# ups.net
KiCad netlist of a schematic drawn in Altium Designer
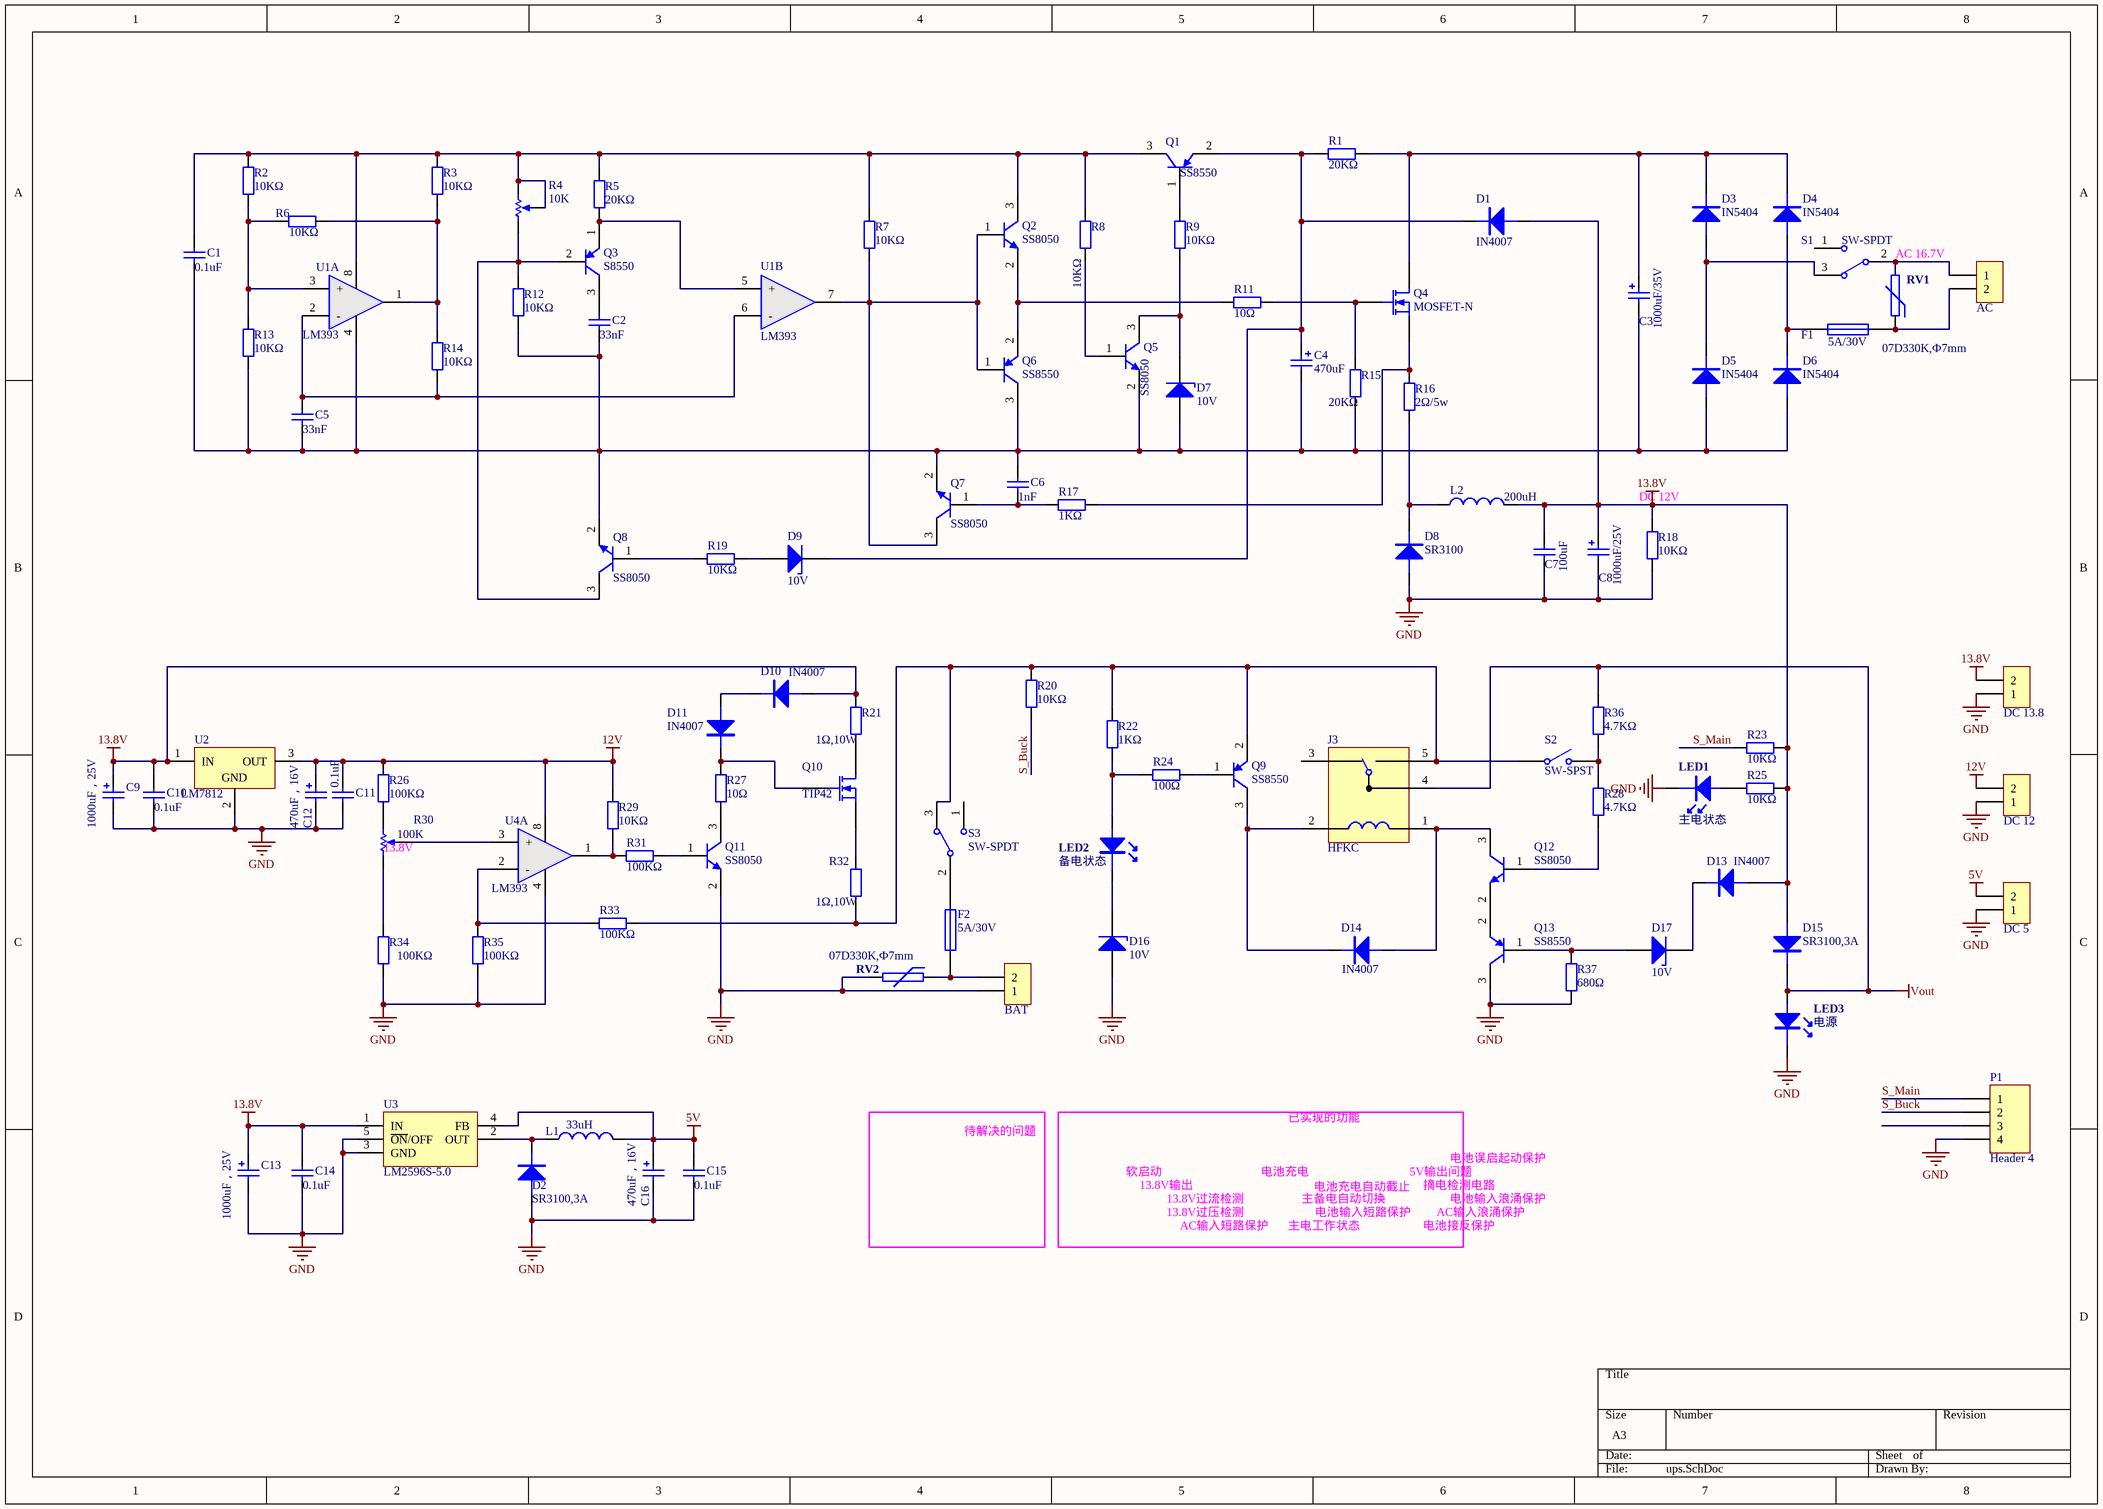
[diagram p0: ups.SchDoc]

(export (version "E")
  (design (tool "Eeschema 10.0.6"))
  (components
    (comp (ref "AC")
      (value "CON2")
      (footprint "CON-2-5.08")
      (description "2EDGR/2EDGK-5.08-2P,DEGSON")
      (libsource (lib "") (part "CON2_1"))
    )
    (comp (ref "BAT")
      (value "CON2")
      (footprint "CON-2-5.08")
      (description "2EDGR/2EDGK-5.08-2P,DEGSON")
      (libsource (lib "IoT-A28LI V1.00") (part "CON2"))
    )
    (comp (ref "C1")
      (value "0.1uF")
      (footprint "C-RAD")
      (description "电容")
      (fields (field (name "PUBLISHER") "Altium Limited"))
      (libsource (lib "liuxiaolong") (part "Cap"))
    )
    (comp (ref "C2")
      (value "33nF")
      (footprint "C-RAD")
      (description "电容")
      (fields (field (name "PUBLISHER") "Altium Limited"))
      (libsource (lib "liuxiaolong") (part "Cap"))
    )
    (comp (ref "C3")
      (value "1000uF/35V")
      (footprint "C-RB-18")
      (description "大容量电容")
      (fields (field (name "PUBLISHER") "Altium Limited"))
      (libsource (lib "liuxiaolong") (part "Cap Pol3"))
    )
    (comp (ref "C4")
      (value "470uF")
      (footprint "C-RB-10")
      (description "大容量电容")
      (fields (field (name "PUBLISHER") "Altium Limited"))
      (libsource (lib "liuxiaolong") (part "Cap Pol3"))
    )
    (comp (ref "C5")
      (value "33nF")
      (footprint "C-RAD")
      (description "电容")
      (fields (field (name "PUBLISHER") "Altium Limited"))
      (libsource (lib "liuxiaolong") (part "Cap"))
    )
    (comp (ref "C6")
      (value "1nF")
      (footprint "C-RAD")
      (description "电容")
      (fields (field (name "PUBLISHER") "Altium Limited"))
      (libsource (lib "liuxiaolong") (part "Cap"))
    )
    (comp (ref "C7")
      (value "100uF")
      (footprint "C-RB-8")
      (description "电容")
      (fields (field (name "PUBLISHER") "Altium Limited"))
      (libsource (lib "liuxiaolong") (part "Cap"))
    )
    (comp (ref "C8")
      (value "1000uF/25V")
      (footprint "C-RB-12")
      (description "大容量电容")
      (fields (field (name "PUBLISHER") "Altium Limited"))
      (libsource (lib "liuxiaolong") (part "Cap Pol3"))
    )
    (comp (ref "C9")
      (value "1000uF，25V")
      (footprint "C-RB-10")
      (description "大容量电容")
      (fields (field (name "PUBLISHER") "Altium Limited"))
      (libsource (lib "liuxiaolong") (part "Cap Pol3"))
    )
    (comp (ref "C10")
      (value "0.1uF")
      (footprint "C-RAD")
      (description "电容")
      (fields (field (name "PUBLISHER") "Altium Limited"))
      (libsource (lib "liuxiaolong") (part "Cap"))
    )
    (comp (ref "C11")
      (value "0.1uF")
      (footprint "C-RAD")
      (description "电容")
      (fields (field (name "PUBLISHER") "Altium Limited"))
      (libsource (lib "liuxiaolong") (part "Cap"))
    )
    (comp (ref "C12")
      (value "470uF，16V")
      (footprint "C-RB-8")
      (description "大容量电容")
      (fields (field (name "PUBLISHER") "Altium Limited"))
      (libsource (lib "liuxiaolong") (part "Cap Pol3"))
    )
    (comp (ref "C13")
      (value "1000uF，25V")
      (footprint "C-RB-10")
      (description "大容量电容")
      (fields (field (name "PUBLISHER") "Altium Limited"))
      (libsource (lib "liuxiaolong") (part "Cap Pol3"))
    )
    (comp (ref "C14")
      (value "0.1uF")
      (footprint "C-RAD")
      (description "电容")
      (fields (field (name "PUBLISHER") "Altium Limited"))
      (libsource (lib "liuxiaolong") (part "Cap"))
    )
    (comp (ref "C15")
      (value "0.1uF")
      (footprint "C-RAD")
      (description "电容")
      (fields (field (name "PUBLISHER") "Altium Limited"))
      (libsource (lib "liuxiaolong") (part "Cap"))
    )
    (comp (ref "C16")
      (value "470uF，16V")
      (footprint "C-RB-8")
      (description "大容量电容")
      (fields (field (name "PUBLISHER") "Altium Limited"))
      (libsource (lib "liuxiaolong") (part "Cap Pol3"))
    )
    (comp (ref "D1")
      (value "IN4007")
      (footprint "DO-41")
      (description "二极管")
      (libsource (lib "liuxiaolong") (part "DIODE"))
    )
    (comp (ref "D2") (value "SR3100,3A") (footprint "DO-201AD") (libsource (lib "xiaofang") (part "DIODE")))
    (comp (ref "D3")
      (value "IN5404")
      (footprint "DO-201AD")
      (description "二极管")
      (libsource (lib "liuxiaolong") (part "DIODE"))
    )
    (comp (ref "D4")
      (value "IN5404")
      (footprint "DO-201AD")
      (description "二极管")
      (libsource (lib "liuxiaolong") (part "DIODE"))
    )
    (comp (ref "D5")
      (value "IN5404")
      (footprint "DO-201AD")
      (description "二极管")
      (libsource (lib "liuxiaolong") (part "DIODE"))
    )
    (comp (ref "D6")
      (value "IN5404")
      (footprint "DO-201AD")
      (description "二极管")
      (libsource (lib "liuxiaolong") (part "DIODE"))
    )
    (comp (ref "D7")
      (value "10V")
      (footprint "DIODE-AXL")
      (description "稳压二极管")
      (fields (field (name "Comment") "Diode-Z") (field (name "PUBLISHER") "Altium Limited"))
      (libsource (lib "fszhang") (part "Diode-Z"))
    )
    (comp (ref "D8")
      (value "SR3100")
      (footprint "DO-201AD")
      (description "二极管")
      (libsource (lib "liuxiaolong") (part "DIODE"))
    )
    (comp (ref "D9")
      (value "10V")
      (footprint "DIODE-AXL")
      (description "稳压二极管")
      (fields (field (name "Comment") "Diode-Z") (field (name "PUBLISHER") "Altium Limited"))
      (libsource (lib "fszhang") (part "Diode-Z"))
    )
    (comp (ref "D10")
      (value "IN4007")
      (footprint "DO-41")
      (description "二极管")
      (libsource (lib "liuxiaolong") (part "DIODE"))
    )
    (comp (ref "D11")
      (value "IN4007")
      (footprint "DO-41")
      (description "二极管")
      (libsource (lib "liuxiaolong") (part "DIODE"))
    )
    (comp (ref "D13")
      (value "IN4007")
      (footprint "DO-41")
      (description "二极管")
      (libsource (lib "liuxiaolong") (part "DIODE"))
    )
    (comp (ref "D14")
      (value "IN4007")
      (footprint "DO-41")
      (description "二极管")
      (libsource (lib "liuxiaolong") (part "DIODE"))
    )
    (comp (ref "D15")
      (value "SR3100,3A")
      (footprint "DO-201AD")
      (description "二极管")
      (libsource (lib "liuxiaolong") (part "DIODE"))
    )
    (comp (ref "D16")
      (value "10V")
      (footprint "DIODE-AXL")
      (description "稳压二极管")
      (fields (field (name "Comment") "Diode-Z") (field (name "PUBLISHER") "Altium Limited"))
      (libsource (lib "fszhang") (part "Diode-Z"))
    )
    (comp (ref "D17")
      (value "10V")
      (footprint "DIODE-AXL")
      (description "稳压二极管")
      (fields (field (name "Comment") "Diode-Z") (field (name "PUBLISHER") "Altium Limited"))
      (libsource (lib "fszhang") (part "Diode-Z"))
    )
    (comp (ref "DC 5")
      (value "CON2")
      (footprint "CON-2-5.08")
      (description "2EDGR/2EDGK-5.08-2P,DEGSON")
      (libsource (lib "IoT-A28LI V1.00") (part "CON2"))
    )
    (comp (ref "DC 12")
      (value "CON2")
      (footprint "CON-2-5.08")
      (description "2EDGR/2EDGK-5.08-2P,DEGSON")
      (libsource (lib "IoT-A28LI V1.00") (part "CON2"))
    )
    (comp (ref "DC 13.8")
      (value "CON2")
      (footprint "CON-2-5.08")
      (description "2EDGR/2EDGK-5.08-2P,DEGSON")
      (libsource (lib "IoT-A28LI V1.00") (part "CON2"))
    )
    (comp (ref "F1")
      (value "5A/30V")
      (footprint "BLX-A")
      (description "Fuse")
      (fields (field (name "PUBLISHER") "Altium Limited"))
      (libsource (lib "Miscellaneous Devices") (part "Fuse 1"))
    )
    (comp (ref "F2")
      (value "5A/30V")
      (footprint "PIN-W2/E2.8")
      (description "Fuse")
      (fields (field (name "PUBLISHER") "Altium Limited"))
      (libsource (lib "Miscellaneous Devices") (part "Fuse 1"))
    )
    (comp (ref "J3")
      (value "HFKC")
      (footprint "HF3FF-12")
      (description "单刀双掷继电器")
      (libsource (lib "fszhang") (part "HFKC"))
    )
    (comp (ref "L1") (value "33uH") (footprint "C-RB-8") (libsource (lib "xiaofang") (part "INDUCTOR")))
    (comp (ref "L2") (value "200uH") (footprint "C-RB-8") (libsource (lib "liuxiaolong") (part "INDUCTOR")))
    (comp (ref "LED1")
      (value "主电状态")
      (footprint "LED_A2")
      (description "红色,0603,0603,*,RoHS")
      (fields (field (name "Comment") "Error"))
      (libsource (lib "IoT-A28LI V1.00") (part "LED1"))
    )
    (comp (ref "LED2")
      (value "备电状态")
      (footprint "LED_A2")
      (description "红色,0603,0603,*,RoHS")
      (fields (field (name "Comment") "Error"))
      (libsource (lib "IoT-A28LI V1.00") (part "LED1"))
    )
    (comp (ref "LED3")
      (value "电源")
      (footprint "LED_A2")
      (description "红色,0603,0603,*,RoHS")
      (fields (field (name "Comment") "Error"))
      (libsource (lib "IoT-A28LI V1.00") (part "LED1"))
    )
    (comp (ref "P1")
      (value "Header 4")
      (footprint "HDR1X4")
      (description "Header, 4-Pin")
      (fields (field (name "PUBLISHER") "Altium Limited"))
      (libsource (lib "Miscellaneous Connectors") (part "Header 4"))
    )
    (comp (ref "Q1")
      (value "SS8550")
      (footprint "TO-92-3")
      (description "PNP贴片三极管")
      (fields (field (name "PUBLISHER") "Altium Limited"))
      (libsource (lib "fszhang") (part "SS8550"))
    )
    (comp (ref "Q2")
      (value "SS8050")
      (footprint "TO-92-3")
      (description "NPN贴片三极管")
      (fields (field (name "PUBLISHER") "Altium Limited"))
      (libsource (lib "fszhang") (part "SS8050"))
    )
    (comp (ref "Q3")
      (value "S8550")
      (footprint "TO-92-3")
      (description "PNP三极管")
      (fields (field (name "PUBLISHER") "Altium Limited"))
      (libsource (lib "fszhang") (part "S8550"))
    )
    (comp (ref "Q4")
      (value "MOSFET-N")
      (footprint "TO-220-3")
      (description "N-Channel MOSFET")
      (fields (field (name "PUBLISHER") "Altium Limited"))
      (libsource (lib "Miscellaneous Devices") (part "MOSFET-N"))
    )
    (comp (ref "Q5")
      (value "SS8050")
      (footprint "TO-92-3")
      (description "NPN贴片三极管")
      (fields (field (name "PUBLISHER") "Altium Limited"))
      (libsource (lib "fszhang") (part "SS8050"))
    )
    (comp (ref "Q6")
      (value "SS8550")
      (footprint "TO-92-3")
      (description "PNP贴片三极管")
      (fields (field (name "PUBLISHER") "Altium Limited"))
      (libsource (lib "fszhang") (part "SS8550"))
    )
    (comp (ref "Q7")
      (value "SS8050")
      (footprint "TO-92-3")
      (description "NPN贴片三极管")
      (fields (field (name "PUBLISHER") "Altium Limited"))
      (libsource (lib "fszhang") (part "SS8050"))
    )
    (comp (ref "Q8")
      (value "SS8050")
      (footprint "TO-92-3")
      (description "NPN贴片三极管")
      (fields (field (name "PUBLISHER") "Altium Limited"))
      (libsource (lib "fszhang") (part "SS8050"))
    )
    (comp (ref "Q9")
      (value "SS8550")
      (footprint "TO-92-3")
      (description "PNP贴片三极管")
      (fields (field (name "PUBLISHER") "Altium Limited"))
      (libsource (lib "fszhang") (part "SS8550"))
    )
    (comp (ref "Q10")
      (value "TIP42")
      (footprint "TO-220-3")
      (description "N-Channel MOSFET")
      (fields (field (name "PUBLISHER") "Altium Limited"))
      (libsource (lib "Miscellaneous Devices") (part "MOSFET-N"))
    )
    (comp (ref "Q11")
      (value "SS8050")
      (footprint "TO-92-3")
      (description "NPN贴片三极管")
      (fields (field (name "PUBLISHER") "Altium Limited"))
      (libsource (lib "fszhang") (part "SS8050"))
    )
    (comp (ref "Q12")
      (value "SS8050")
      (footprint "TO-92-3")
      (description "NPN贴片三极管")
      (fields (field (name "PUBLISHER") "Altium Limited"))
      (libsource (lib "fszhang") (part "SS8050"))
    )
    (comp (ref "Q13")
      (value "SS8550")
      (footprint "TO-92-3")
      (description "PNP贴片三极管")
      (fields (field (name "PUBLISHER") "Altium Limited"))
      (libsource (lib "fszhang") (part "SS8550"))
    )
    (comp (ref "R1")
      (value "20KΩ")
      (footprint "AXIAL-0.4")
      (description "电阻")
      (fields (field (name "PUBLISHER") "Altium Limited"))
      (libsource (lib "") (part "Res2_2"))
    )
    (comp (ref "R2")
      (value "10KΩ")
      (footprint "AXIAL-0.4")
      (description "电阻")
      (fields (field (name "PUBLISHER") "Altium Limited"))
      (libsource (lib "") (part "Res2_1"))
    )
    (comp (ref "R3")
      (value "10KΩ")
      (footprint "AXIAL-0.4")
      (description "电阻")
      (fields (field (name "PUBLISHER") "Altium Limited"))
      (libsource (lib "") (part "Res2_1"))
    )
    (comp (ref "R4")
      (value "10K")
      (footprint "VR_A1")
      (description "精密可调电阻")
      (fields (field (name "Comment") "RPot") (field (name "PUBLISHER") "Altium Limited"))
      (libsource (lib "fszhang") (part "RPot"))
    )
    (comp (ref "R5")
      (value "20KΩ")
      (footprint "AXIAL-0.4")
      (description "电阻")
      (fields (field (name "PUBLISHER") "Altium Limited"))
      (libsource (lib "") (part "Res2_1"))
    )
    (comp (ref "R6")
      (value "10KΩ")
      (footprint "AXIAL-0.4")
      (description "电阻")
      (fields (field (name "PUBLISHER") "Altium Limited"))
      (libsource (lib "") (part "Res2_3"))
    )
    (comp (ref "R7")
      (value "10KΩ")
      (footprint "AXIAL-0.4")
      (description "电阻")
      (fields (field (name "PUBLISHER") "Altium Limited"))
      (libsource (lib "") (part "Res2_1"))
    )
    (comp (ref "R8")
      (value "10KΩ")
      (footprint "AXIAL-0.4")
      (description "电阻")
      (fields (field (name "PUBLISHER") "Altium Limited"))
      (libsource (lib "liuxiaolong") (part "Res2"))
    )
    (comp (ref "R9")
      (value "10KΩ")
      (footprint "AXIAL-0.4")
      (description "电阻")
      (fields (field (name "PUBLISHER") "Altium Limited"))
      (libsource (lib "liuxiaolong") (part "Res2"))
    )
    (comp (ref "R11")
      (value "10Ω")
      (footprint "AXIAL-0.4")
      (description "电阻")
      (fields (field (name "PUBLISHER") "Altium Limited"))
      (libsource (lib "") (part "Res2_2"))
    )
    (comp (ref "R12")
      (value "10KΩ")
      (footprint "AXIAL-0.4")
      (description "电阻")
      (fields (field (name "PUBLISHER") "Altium Limited"))
      (libsource (lib "") (part "Res2_1"))
    )
    (comp (ref "R13")
      (value "10KΩ")
      (footprint "AXIAL-0.4")
      (description "电阻")
      (fields (field (name "PUBLISHER") "Altium Limited"))
      (libsource (lib "") (part "Res2_1"))
    )
    (comp (ref "R14")
      (value "10KΩ")
      (footprint "AXIAL-0.4")
      (description "电阻")
      (fields (field (name "PUBLISHER") "Altium Limited"))
      (libsource (lib "") (part "Res2_1"))
    )
    (comp (ref "R15")
      (value "20KΩ")
      (footprint "AXIAL-0.4")
      (description "电阻")
      (fields (field (name "PUBLISHER") "Altium Limited"))
      (libsource (lib "liuxiaolong") (part "Res2"))
    )
    (comp (ref "R16")
      (value "2Ω/5w")
      (footprint "AXIAL-1.0")
      (description "电阻")
      (fields (field (name "PUBLISHER") "Altium Limited"))
      (libsource (lib "liuxiaolong") (part "Res2"))
    )
    (comp (ref "R17")
      (value "1KΩ")
      (footprint "AXIAL-0.4")
      (description "电阻")
      (fields (field (name "PUBLISHER") "Altium Limited"))
      (libsource (lib "") (part "Res2_2"))
    )
    (comp (ref "R18")
      (value "10KΩ")
      (footprint "AXIAL-0.4")
      (description "电阻")
      (fields (field (name "PUBLISHER") "Altium Limited"))
      (libsource (lib "") (part "Res2_3"))
    )
    (comp (ref "R19")
      (value "10KΩ")
      (footprint "AXIAL-0.4")
      (description "电阻")
      (fields (field (name "PUBLISHER") "Altium Limited"))
      (libsource (lib "") (part "Res2_2"))
    )
    (comp (ref "R20")
      (value "10KΩ")
      (footprint "AXIAL-0.4")
      (description "电阻")
      (fields (field (name "PUBLISHER") "Altium Limited"))
      (libsource (lib "") (part "Res2_3"))
    )
    (comp (ref "R21")
      (value "1Ω,10W")
      (footprint "AXIAL-1.0")
      (description "电阻")
      (fields (field (name "PUBLISHER") "Altium Limited"))
      (libsource (lib "liuxiaolong") (part "Res2"))
    )
    (comp (ref "R22")
      (value "1KΩ")
      (footprint "AXIAL-0.4")
      (description "电阻")
      (fields (field (name "PUBLISHER") "Altium Limited"))
      (libsource (lib "") (part "Res2_3"))
    )
    (comp (ref "R23")
      (value "10KΩ")
      (footprint "AXIAL-0.4")
      (description "电阻")
      (fields (field (name "PUBLISHER") "Altium Limited"))
      (libsource (lib "liuxiaolong") (part "Res2"))
    )
    (comp (ref "R24")
      (value "100Ω")
      (footprint "AXIAL-0.4")
      (description "电阻")
      (fields (field (name "PUBLISHER") "Altium Limited"))
      (libsource (lib "") (part "Res2_1"))
    )
    (comp (ref "R25")
      (value "10KΩ")
      (footprint "AXIAL-0.4")
      (description "电阻")
      (fields (field (name "PUBLISHER") "Altium Limited"))
      (libsource (lib "liuxiaolong") (part "Res2"))
    )
    (comp (ref "R26")
      (value "100KΩ")
      (footprint "AXIAL-0.4")
      (description "电阻")
      (fields (field (name "PUBLISHER") "Altium Limited"))
      (libsource (lib "") (part "Res2_1"))
    )
    (comp (ref "R27")
      (value "10Ω")
      (footprint "AXIAL-0.4")
      (description "电阻")
      (fields (field (name "PUBLISHER") "Altium Limited"))
      (libsource (lib "liuxiaolong") (part "Res2"))
    )
    (comp (ref "R28")
      (value "4.7KΩ")
      (footprint "AXIAL-0.4")
      (description "电阻")
      (fields (field (name "PUBLISHER") "Altium Limited"))
      (libsource (lib "") (part "Res2_2"))
    )
    (comp (ref "R29")
      (value "10KΩ")
      (footprint "AXIAL-0.4")
      (description "电阻")
      (fields (field (name "PUBLISHER") "Altium Limited"))
      (libsource (lib "") (part "Res2_1"))
    )
    (comp (ref "R30")
      (value "100K")
      (footprint "VR_A1")
      (description "精密可调电阻")
      (fields (field (name "Comment") "RPot") (field (name "PUBLISHER") "Altium Limited"))
      (libsource (lib "fszhang") (part "RPot"))
    )
    (comp (ref "R31")
      (value "100KΩ")
      (footprint "AXIAL-0.4")
      (description "电阻")
      (fields (field (name "PUBLISHER") "Altium Limited"))
      (libsource (lib "") (part "Res2_2"))
    )
    (comp (ref "R32")
      (value "1Ω,10W")
      (footprint "AXIAL-1.0")
      (description "电阻")
      (fields (field (name "PUBLISHER") "Altium Limited"))
      (libsource (lib "liuxiaolong") (part "Res2"))
    )
    (comp (ref "R33")
      (value "100KΩ")
      (footprint "AXIAL-0.4")
      (description "电阻")
      (fields (field (name "PUBLISHER") "Altium Limited"))
      (libsource (lib "") (part "Res2_2"))
    )
    (comp (ref "R34")
      (value "100KΩ")
      (footprint "AXIAL-0.4")
      (description "电阻")
      (fields (field (name "PUBLISHER") "Altium Limited"))
      (libsource (lib "") (part "Res2_1"))
    )
    (comp (ref "R35")
      (value "100KΩ")
      (footprint "AXIAL-0.4")
      (description "电阻")
      (fields (field (name "PUBLISHER") "Altium Limited"))
      (libsource (lib "") (part "Res2_1"))
    )
    (comp (ref "R36")
      (value "4.7KΩ")
      (footprint "AXIAL-0.4")
      (description "电阻")
      (fields (field (name "PUBLISHER") "Altium Limited"))
      (libsource (lib "") (part "Res2_2"))
    )
    (comp (ref "R37")
      (value "680Ω")
      (footprint "AXIAL-0.4")
      (description "电阻")
      (fields (field (name "PUBLISHER") "Altium Limited"))
      (libsource (lib "") (part "Res2_3"))
    )
    (comp (ref "RV1")
      (value "07D330K,Ф7mm")
      (footprint "AX-5P-9DX4.6T")
      (description "220KD07,Ф8×3mm,RoHS")
      (libsource (lib "IoT-A28LI V1.00") (part "RES4"))
    )
    (comp (ref "RV2")
      (value "07D330K,Ф7mm")
      (footprint "AX-5P-9DX4.6T")
      (description "220KD07,Ф8×3mm,RoHS")
      (libsource (lib "IoT-A28LI V1.00") (part "RES4"))
    )
    (comp (ref "S1")
      (value "SW-SPDT")
      (footprint "SWITCH_A3")
      (description "开关")
      (fields (field (name "PUBLISHER") "Altium Limited"))
      (libsource (lib "fszhang") (part "SW-SPDT"))
    )
    (comp (ref "S2")
      (value "SW-SPST")
      (footprint "SW_4")
      (description "Single-Pole, Single-Throw Switch")
      (fields (field (name "PUBLISHER") "Altium Limited"))
      (libsource (lib "Miscellaneous Devices") (part "SW-SPST"))
    )
    (comp (ref "S3")
      (value "SW-SPDT")
      (footprint "SWITCH_A3")
      (description "开关")
      (fields (field (name "PUBLISHER") "Altium Limited"))
      (libsource (lib "fszhang") (part "SW-SPDT"))
    )
    (comp (ref "U1")
      (value "LM393")
      (footprint "DIP-8")
      (description "比较器，2")
      (libsource (lib "liuxiaolong") (part "LM393"))
    )
    (comp (ref "U2")
      (value "LM7812")
      (footprint "TO-220-3")
      (description "Series 3-Terminal Positive Regulator")
      (fields (field (name "PUBLISHER") "Altium Limited"))
      (libsource (lib "fszhang") (part "LM7818CT"))
    )
    (comp (ref "U3")
      (value "LM2596S-5.0")
      (footprint "TO-220-5A")
      (description "Simple Switcher Power Converter 150 kHz 3A Step Down Voltage Regulator")
      (fields (field (name "PUBLISHER") "Altium Limited"))
      (libsource (lib "电路扫描原理图") (part "LM2596S-5.0"))
    )
    (comp (ref "U4")
      (value "LM393")
      (footprint "DIP-8")
      (description "比较器，2")
      (libsource (lib "liuxiaolong") (part "LM393"))
    )
  )
  (nets
    (net (code "2") (name "/S_Buck") (class "Default")
      (node (ref "P1") (pin "2") (pinfunction "2_2") (pintype "passive"))
      (node (ref "R20") (pin "2") (pinfunction "2_2") (pintype "passive"))
    )
    (net (code "3") (name "/S_Main") (class "Default")
      (node (ref "P1") (pin "1") (pinfunction "1_1") (pintype "passive"))
      (node (ref "R23") (pin "2") (pinfunction "2_2") (pintype "passive"))
    )
    (net (code "4") (name "5V") (class "Default")
      (node (ref "C15") (pin "2") (pinfunction "2_2") (pintype "passive"))
      (node (ref "C16") (pin "1") (pinfunction "1_1") (pintype "passive"))
      (node (ref "DC 5") (pin "2") (pinfunction "2_2") (pintype "passive"))
      (node (ref "L1") (pin "2") (pinfunction "2_2") (pintype "passive"))
      (node (ref "U3") (pin "4") (pinfunction "FB_4") (pintype "passive"))
    )
    (net (code "5") (name "12V") (class "Default")
      (node (ref "C11") (pin "2") (pinfunction "2_2") (pintype "passive"))
      (node (ref "C12") (pin "1") (pinfunction "1_1") (pintype "passive"))
      (node (ref "DC 12") (pin "2") (pinfunction "2_2") (pintype "passive"))
      (node (ref "R26") (pin "2") (pinfunction "2_2") (pintype "passive"))
      (node (ref "R29") (pin "2") (pinfunction "2_2") (pintype "passive"))
      (node (ref "U2") (pin "3") (pinfunction "OUT_3") (pintype "power_in"))
      (node (ref "U4") (pin "8") (pinfunction "VCC_8") (pintype "power_in"))
    )
    (net (code "6") (name "13.8V") (class "Default")
      (node (ref "C10") (pin "2") (pinfunction "2_2") (pintype "passive"))
      (node (ref "C13") (pin "1") (pinfunction "1_1") (pintype "passive"))
      (node (ref "C14") (pin "2") (pinfunction "2_2") (pintype "passive"))
      (node (ref "C7") (pin "2") (pinfunction "2_2") (pintype "passive"))
      (node (ref "C8") (pin "1") (pinfunction "1_1") (pintype "passive"))
      (node (ref "C9") (pin "1") (pinfunction "1_1") (pintype "passive"))
      (node (ref "D1") (pin "1") (pinfunction "A_1") (pintype "passive"))
      (node (ref "D10") (pin "1") (pinfunction "A_1") (pintype "passive"))
      (node (ref "D13") (pin "1") (pinfunction "A_1") (pintype "passive"))
      (node (ref "D15") (pin "1") (pinfunction "A_1") (pintype "passive"))
      (node (ref "DC 13.8") (pin "2") (pinfunction "2_2") (pintype "passive"))
      (node (ref "L2") (pin "1") (pinfunction "1_1") (pintype "passive"))
      (node (ref "R18") (pin "1") (pinfunction "1_1") (pintype "passive"))
      (node (ref "R21") (pin "1") (pinfunction "1_1") (pintype "passive"))
      (node (ref "R23") (pin "1") (pinfunction "1_1") (pintype "passive"))
      (node (ref "R25") (pin "1") (pinfunction "1_1") (pintype "passive"))
      (node (ref "U2") (pin "1") (pinfunction "IN_1") (pintype "power_in"))
      (node (ref "U3") (pin "1") (pinfunction "IN_1") (pintype "power_in"))
    )
    (net (code "7") (name "GND") (class "Default")
      (node (ref "BAT") (pin "1") (pinfunction "1_1") (pintype "passive"))
      (node (ref "C10") (pin "1") (pinfunction "1_1") (pintype "passive"))
      (node (ref "C11") (pin "1") (pinfunction "1_1") (pintype "passive"))
      (node (ref "C12") (pin "2") (pinfunction "2_2") (pintype "passive"))
      (node (ref "C13") (pin "2") (pinfunction "2_2") (pintype "passive"))
      (node (ref "C14") (pin "1") (pinfunction "1_1") (pintype "passive"))
      (node (ref "C15") (pin "1") (pinfunction "1_1") (pintype "passive"))
      (node (ref "C16") (pin "2") (pinfunction "2_2") (pintype "passive"))
      (node (ref "C7") (pin "1") (pinfunction "1_1") (pintype "passive"))
      (node (ref "C8") (pin "2") (pinfunction "2_2") (pintype "passive"))
      (node (ref "C9") (pin "2") (pinfunction "2_2") (pintype "passive"))
      (node (ref "D16") (pin "1") (pinfunction "A_1") (pintype "passive"))
      (node (ref "D2") (pin "1") (pinfunction "A_1") (pintype "passive"))
      (node (ref "D8") (pin "1") (pinfunction "A_1") (pintype "passive"))
      (node (ref "DC 12") (pin "1") (pinfunction "1_1") (pintype "passive"))
      (node (ref "DC 13.8") (pin "1") (pinfunction "1_1") (pintype "passive"))
      (node (ref "DC 5") (pin "1") (pinfunction "1_1") (pintype "passive"))
      (node (ref "LED1") (pin "2") (pinfunction "2_2") (pintype "passive"))
      (node (ref "LED3") (pin "2") (pinfunction "2_2") (pintype "passive"))
      (node (ref "P1") (pin "4") (pinfunction "4_4") (pintype "passive"))
      (node (ref "Q11") (pin "2") (pinfunction "E_2") (pintype "passive"))
      (node (ref "Q13") (pin "3") (pinfunction "C_3") (pintype "passive"))
      (node (ref "R18") (pin "2") (pinfunction "2_2") (pintype "passive"))
      (node (ref "R34") (pin "1") (pinfunction "1_1") (pintype "passive"))
      (node (ref "R35") (pin "1") (pinfunction "1_1") (pintype "passive"))
      (node (ref "R37") (pin "2") (pinfunction "2_2") (pintype "passive"))
      (node (ref "RV2") (pin "2") (pinfunction "2_2") (pintype "passive"))
      (node (ref "U2") (pin "2") (pinfunction "GND_2") (pintype "power_in"))
      (node (ref "U3") (pin "3") (pinfunction "GND_3") (pintype "power_in"))
      (node (ref "U3") (pin "5") (pinfunction "~{ON}/OFF_5") (pintype "passive"))
      (node (ref "U4") (pin "4") (pinfunction "GND_4") (pintype "power_in"))
    )
    (net (code "8") (name "Net-(AC-Pad1)") (class "Default")
      (node (ref "AC") (pin "1") (pinfunction "1_1") (pintype "passive"))
      (node (ref "RV1") (pin "2") (pinfunction "2_2") (pintype "passive"))
      (node (ref "S1") (pin "2") (pinfunction "2_2") (pintype "passive"))
    )
    (net (code "9") (name "Net-(AC-Pad2)") (class "Default")
      (node (ref "AC") (pin "2") (pinfunction "2_2") (pintype "passive"))
      (node (ref "F1") (pin "1") (pinfunction "1_1") (pintype "passive"))
      (node (ref "RV1") (pin "1") (pinfunction "1_1") (pintype "passive"))
    )
    (net (code "10") (name "Net-(BAT-Pad2)") (class "Default")
      (node (ref "BAT") (pin "2") (pinfunction "2_2") (pintype "passive"))
      (node (ref "F2") (pin "2") (pinfunction "2_2") (pintype "passive"))
      (node (ref "RV2") (pin "1") (pinfunction "1_1") (pintype "passive"))
    )
    (net (code "11") (name "Net-(D1-K)") (class "Default")
      (node (ref "C4") (pin "1") (pinfunction "1_1") (pintype "passive"))
      (node (ref "D1") (pin "2") (pinfunction "K_2") (pintype "passive"))
      (node (ref "D9") (pin "2") (pinfunction "K_2") (pintype "passive"))
      (node (ref "Q1") (pin "2") (pinfunction "E_2") (pintype "passive"))
      (node (ref "R1") (pin "1") (pinfunction "1_1") (pintype "passive"))
    )
    (net (code "12") (name "Net-(D2-K)") (class "Default")
      (node (ref "D2") (pin "2") (pinfunction "K_2") (pintype "passive"))
      (node (ref "L1") (pin "1") (pinfunction "1_1") (pintype "passive"))
      (node (ref "U3") (pin "2") (pinfunction "OUT_2") (pintype "power_in"))
    )
    (net (code "13") (name "Net-(D3-A)") (class "Default")
      (node (ref "D3") (pin "1") (pinfunction "A_1") (pintype "passive"))
      (node (ref "D5") (pin "2") (pinfunction "K_2") (pintype "passive"))
      (node (ref "S1") (pin "3") (pinfunction "3_3") (pintype "passive"))
    )
    (net (code "14") (name "Net-(D3-K)") (class "Default")
      (node (ref "C3") (pin "1") (pinfunction "1_1") (pintype "passive"))
      (node (ref "D3") (pin "2") (pinfunction "K_2") (pintype "passive"))
      (node (ref "D4") (pin "2") (pinfunction "K_2") (pintype "passive"))
      (node (ref "Q4") (pin "1") (pinfunction "D_1") (pintype "passive"))
      (node (ref "R1") (pin "2") (pinfunction "2_2") (pintype "passive"))
    )
    (net (code "15") (name "Net-(D4-A)") (class "Default")
      (node (ref "D4") (pin "1") (pinfunction "A_1") (pintype "passive"))
      (node (ref "D6") (pin "2") (pinfunction "K_2") (pintype "passive"))
      (node (ref "F1") (pin "2") (pinfunction "2_2") (pintype "passive"))
    )
    (net (code "16") (name "Net-(D5-A)") (class "Default")
      (node (ref "C1") (pin "1") (pinfunction "1_1") (pintype "passive"))
      (node (ref "C2") (pin "1") (pinfunction "1_1") (pintype "passive"))
      (node (ref "C3") (pin "2") (pinfunction "2_2") (pintype "passive"))
      (node (ref "C4") (pin "2") (pinfunction "2_2") (pintype "passive"))
      (node (ref "C5") (pin "1") (pinfunction "1_1") (pintype "passive"))
      (node (ref "C6") (pin "2") (pinfunction "2_2") (pintype "passive"))
      (node (ref "D5") (pin "1") (pinfunction "A_1") (pintype "passive"))
      (node (ref "D6") (pin "1") (pinfunction "A_1") (pintype "passive"))
      (node (ref "D7") (pin "1") (pinfunction "A_1") (pintype "passive"))
      (node (ref "Q5") (pin "2") (pinfunction "E_2") (pintype "passive"))
      (node (ref "Q6") (pin "3") (pinfunction "C_3") (pintype "passive"))
      (node (ref "Q7") (pin "2") (pinfunction "E_2") (pintype "passive"))
      (node (ref "Q8") (pin "2") (pinfunction "E_2") (pintype "passive"))
      (node (ref "R12") (pin "1") (pinfunction "1_1") (pintype "passive"))
      (node (ref "R13") (pin "1") (pinfunction "1_1") (pintype "passive"))
      (node (ref "R15") (pin "2") (pinfunction "2_2") (pintype "passive"))
      (node (ref "U1") (pin "4") (pinfunction "GND_4") (pintype "power_in"))
    )
    (net (code "17") (name "Net-(D7-K)") (class "Default")
      (node (ref "D7") (pin "2") (pinfunction "K_2") (pintype "passive"))
      (node (ref "Q5") (pin "3") (pinfunction "C_3") (pintype "passive"))
      (node (ref "R9") (pin "2") (pinfunction "2_2") (pintype "passive"))
    )
    (net (code "18") (name "Net-(D8-K)") (class "Default")
      (node (ref "D8") (pin "2") (pinfunction "K_2") (pintype "passive"))
      (node (ref "L2") (pin "2") (pinfunction "2_2") (pintype "passive"))
      (node (ref "R16") (pin "2") (pinfunction "2_2") (pintype "passive"))
    )
    (net (code "19") (name "Net-(D9-A)") (class "Default")
      (node (ref "D9") (pin "1") (pinfunction "A_1") (pintype "passive"))
      (node (ref "R19") (pin "2") (pinfunction "2_2") (pintype "passive"))
    )
    (net (code "20") (name "Net-(D10-K)") (class "Default")
      (node (ref "D10") (pin "2") (pinfunction "K_2") (pintype "passive"))
      (node (ref "D11") (pin "1") (pinfunction "A_1") (pintype "passive"))
    )
    (net (code "21") (name "Net-(D11-K)") (class "Default")
      (node (ref "D11") (pin "2") (pinfunction "K_2") (pintype "passive"))
      (node (ref "Q10") (pin "2") (pinfunction "G_2") (pintype "passive"))
      (node (ref "R27") (pin "1") (pinfunction "1_1") (pintype "passive"))
    )
    (net (code "22") (name "Net-(D13-K)") (class "Default")
      (node (ref "D13") (pin "2") (pinfunction "K_2") (pintype "passive"))
      (node (ref "D17") (pin "2") (pinfunction "K_2") (pintype "passive"))
    )
    (net (code "23") (name "Net-(D14-A)") (class "Default")
      (node (ref "D14") (pin "1") (pinfunction "A_1") (pintype "passive"))
      (node (ref "J3") (pin "1") (pinfunction "1_1") (pintype "passive"))
      (node (ref "Q12") (pin "3") (pinfunction "C_3") (pintype "passive"))
    )
    (net (code "24") (name "Net-(D14-K)") (class "Default")
      (node (ref "D14") (pin "2") (pinfunction "K_2") (pintype "passive"))
      (node (ref "J3") (pin "2") (pinfunction "2_2") (pintype "passive"))
      (node (ref "Q9") (pin "3") (pinfunction "C_3") (pintype "passive"))
    )
    (net (code "25") (name "Net-(D16-K)") (class "Default")
      (node (ref "D16") (pin "2") (pinfunction "K_2") (pintype "passive"))
      (node (ref "LED2") (pin "2") (pinfunction "2_2") (pintype "passive"))
    )
    (net (code "26") (name "Net-(D17-A)") (class "Default")
      (node (ref "D17") (pin "1") (pinfunction "A_1") (pintype "passive"))
      (node (ref "Q13") (pin "1") (pinfunction "B_1") (pintype "passive"))
      (node (ref "R37") (pin "1") (pinfunction "1_1") (pintype "passive"))
    )
    (net (code "27") (name "Net-(F2-Pad1)") (class "Default")
      (node (ref "F2") (pin "1") (pinfunction "1_1") (pintype "passive"))
      (node (ref "S3") (pin "2") (pinfunction "2_2") (pintype "passive"))
    )
    (net (code "28") (name "Net-(LED1-Pad1)") (class "Default")
      (node (ref "LED1") (pin "1") (pinfunction "1_1") (pintype "passive"))
      (node (ref "R25") (pin "2") (pinfunction "2_2") (pintype "passive"))
    )
    (net (code "29") (name "Net-(LED2-Pad1)") (class "Default")
      (node (ref "LED2") (pin "1") (pinfunction "1_1") (pintype "passive"))
      (node (ref "R22") (pin "2") (pinfunction "2_2") (pintype "passive"))
      (node (ref "R24") (pin "1") (pinfunction "1_1") (pintype "passive"))
    )
    (net (code "30") (name "Net-(Q1-B)") (class "Default")
      (node (ref "Q1") (pin "1") (pinfunction "B_1") (pintype "passive"))
      (node (ref "R9") (pin "1") (pinfunction "1_1") (pintype "passive"))
    )
    (net (code "31") (name "Net-(Q1-C)") (class "Default")
      (node (ref "C1") (pin "2") (pinfunction "2_2") (pintype "passive"))
      (node (ref "Q1") (pin "3") (pinfunction "C_3") (pintype "passive"))
      (node (ref "Q2") (pin "3") (pinfunction "C_3") (pintype "passive"))
      (node (ref "R2") (pin "2") (pinfunction "2_2") (pintype "passive"))
      (node (ref "R3") (pin "2") (pinfunction "2_2") (pintype "passive"))
      (node (ref "R4") (pin "2") (pinfunction "TAP_2") (pintype "passive"))
      (node (ref "R4") (pin "3") (pinfunction "BOT_3") (pintype "passive"))
      (node (ref "R5") (pin "2") (pinfunction "2_2") (pintype "passive"))
      (node (ref "R7") (pin "2") (pinfunction "2_2") (pintype "passive"))
      (node (ref "R8") (pin "1") (pinfunction "1_1") (pintype "passive"))
      (node (ref "U1") (pin "8") (pinfunction "VCC_8") (pintype "power_in"))
    )
    (net (code "32") (name "Net-(Q2-B)") (class "Default")
      (node (ref "Q2") (pin "1") (pinfunction "B_1") (pintype "passive"))
      (node (ref "Q6") (pin "1") (pinfunction "B_1") (pintype "passive"))
      (node (ref "Q7") (pin "3") (pinfunction "C_3") (pintype "passive"))
      (node (ref "R7") (pin "1") (pinfunction "1_1") (pintype "passive"))
      (node (ref "U1") (pin "7") (pinfunction "OUT2_7") (pintype "passive"))
    )
    (net (code "33") (name "Net-(Q2-E)") (class "Default")
      (node (ref "Q2") (pin "2") (pinfunction "E_2") (pintype "passive"))
      (node (ref "Q6") (pin "2") (pinfunction "E_2") (pintype "passive"))
      (node (ref "R11") (pin "1") (pinfunction "1_1") (pintype "passive"))
    )
    (net (code "34") (name "Net-(Q3-B)") (class "Default")
      (node (ref "Q3") (pin "2") (pinfunction "B_2") (pintype "passive"))
      (node (ref "Q8") (pin "3") (pinfunction "C_3") (pintype "passive"))
      (node (ref "R12") (pin "2") (pinfunction "2_2") (pintype "passive"))
      (node (ref "R4") (pin "1") (pinfunction "TOP_1") (pintype "passive"))
    )
    (net (code "35") (name "Net-(Q3-C)") (class "Default")
      (node (ref "C2") (pin "2") (pinfunction "2_2") (pintype "passive"))
      (node (ref "Q3") (pin "3") (pinfunction "C_3") (pintype "passive"))
    )
    (net (code "36") (name "Net-(Q3-E)") (class "Default")
      (node (ref "Q3") (pin "1") (pinfunction "E_1") (pintype "passive"))
      (node (ref "R5") (pin "1") (pinfunction "1_1") (pintype "passive"))
      (node (ref "U1") (pin "5") (pinfunction "+_5") (pintype "passive"))
    )
    (net (code "37") (name "Net-(Q4-G)") (class "Default")
      (node (ref "Q4") (pin "2") (pinfunction "G_2") (pintype "passive"))
      (node (ref "R11") (pin "2") (pinfunction "2_2") (pintype "passive"))
      (node (ref "R15") (pin "1") (pinfunction "1_1") (pintype "passive"))
    )
    (net (code "38") (name "Net-(Q4-S)") (class "Default")
      (node (ref "Q4") (pin "3") (pinfunction "S_3") (pintype "passive"))
      (node (ref "R16") (pin "1") (pinfunction "1_1") (pintype "passive"))
      (node (ref "R17") (pin "2") (pinfunction "2_2") (pintype "passive"))
    )
    (net (code "39") (name "Net-(Q5-B)") (class "Default")
      (node (ref "Q5") (pin "1") (pinfunction "B_1") (pintype "passive"))
      (node (ref "R8") (pin "2") (pinfunction "2_2") (pintype "passive"))
    )
    (net (code "40") (name "Net-(Q7-B)") (class "Default")
      (node (ref "C6") (pin "1") (pinfunction "1_1") (pintype "passive"))
      (node (ref "Q7") (pin "1") (pinfunction "B_1") (pintype "passive"))
      (node (ref "R17") (pin "1") (pinfunction "1_1") (pintype "passive"))
    )
    (net (code "41") (name "Net-(Q8-B)") (class "Default")
      (node (ref "Q8") (pin "1") (pinfunction "B_1") (pintype "passive"))
      (node (ref "R19") (pin "1") (pinfunction "1_1") (pintype "passive"))
    )
    (net (code "42") (name "Net-(Q9-B)") (class "Default")
      (node (ref "Q9") (pin "1") (pinfunction "B_1") (pintype "passive"))
      (node (ref "R24") (pin "2") (pinfunction "2_2") (pintype "passive"))
    )
    (net (code "43") (name "Net-(Q9-E)") (class "Default")
      (node (ref "J3") (pin "5") (pinfunction "5_5") (pintype "passive"))
      (node (ref "Q9") (pin "2") (pinfunction "E_2") (pintype "passive"))
      (node (ref "R20") (pin "1") (pinfunction "1_1") (pintype "passive"))
      (node (ref "R22") (pin "1") (pinfunction "1_1") (pintype "passive"))
      (node (ref "R32") (pin "2") (pinfunction "2_2") (pintype "passive"))
      (node (ref "R33") (pin "2") (pinfunction "2_2") (pintype "passive"))
      (node (ref "S2") (pin "1") (pinfunction "COMMON_1") (pintype "passive"))
      (node (ref "S3") (pin "3") (pinfunction "3_3") (pintype "passive"))
    )
    (net (code "44") (name "Net-(Q10-D)") (class "Default")
      (node (ref "Q10") (pin "1") (pinfunction "D_1") (pintype "passive"))
      (node (ref "R21") (pin "2") (pinfunction "2_2") (pintype "passive"))
    )
    (net (code "45") (name "Net-(Q10-S)") (class "Default")
      (node (ref "Q10") (pin "3") (pinfunction "S_3") (pintype "passive"))
      (node (ref "R32") (pin "1") (pinfunction "1_1") (pintype "passive"))
    )
    (net (code "46") (name "Net-(Q11-B)") (class "Default")
      (node (ref "Q11") (pin "1") (pinfunction "B_1") (pintype "passive"))
      (node (ref "R31") (pin "2") (pinfunction "2_2") (pintype "passive"))
    )
    (net (code "47") (name "Net-(Q11-C)") (class "Default")
      (node (ref "Q11") (pin "3") (pinfunction "C_3") (pintype "passive"))
      (node (ref "R27") (pin "2") (pinfunction "2_2") (pintype "passive"))
    )
    (net (code "48") (name "Net-(Q12-B)") (class "Default")
      (node (ref "Q12") (pin "1") (pinfunction "B_1") (pintype "passive"))
      (node (ref "R28") (pin "1") (pinfunction "1_1") (pintype "passive"))
    )
    (net (code "49") (name "Net-(Q12-E)") (class "Default")
      (node (ref "Q12") (pin "2") (pinfunction "E_2") (pintype "passive"))
      (node (ref "Q13") (pin "2") (pinfunction "E_2") (pintype "passive"))
    )
    (net (code "50") (name "Net-(R30-BOT)") (class "Default")
      (node (ref "R26") (pin "1") (pinfunction "1_1") (pintype "passive"))
      (node (ref "R30") (pin "3") (pinfunction "BOT_3") (pintype "passive"))
    )
    (net (code "51") (name "Net-(R30-TAP)") (class "Default")
      (node (ref "R30") (pin "2") (pinfunction "TAP_2") (pintype "passive"))
      (node (ref "U4") (pin "3") (pinfunction "+_3") (pintype "passive"))
    )
    (net (code "52") (name "Net-(R30-TOP)") (class "Default")
      (node (ref "R30") (pin "1") (pinfunction "TOP_1") (pintype "passive"))
      (node (ref "R34") (pin "2") (pinfunction "2_2") (pintype "passive"))
    )
    (net (code "53") (name "Net-(S2-NO)") (class "Default")
      (node (ref "R28") (pin "2") (pinfunction "2_2") (pintype "passive"))
      (node (ref "R36") (pin "1") (pinfunction "1_1") (pintype "passive"))
      (node (ref "S2") (pin "2") (pinfunction "NO_2") (pintype "passive"))
    )
    (net (code "54") (name "Net-(U1A-+)") (class "Default")
      (node (ref "R13") (pin "2") (pinfunction "2_2") (pintype "passive"))
      (node (ref "R2") (pin "1") (pinfunction "1_1") (pintype "passive"))
      (node (ref "R6") (pin "2") (pinfunction "2_2") (pintype "passive"))
      (node (ref "U1") (pin "3") (pinfunction "+_3") (pintype "passive"))
    )
    (net (code "55") (name "Net-(U1A--)") (class "Default")
      (node (ref "C5") (pin "2") (pinfunction "2_2") (pintype "passive"))
      (node (ref "R14") (pin "1") (pinfunction "1_1") (pintype "passive"))
      (node (ref "U1") (pin "2") (pinfunction "-_2") (pintype "passive"))
      (node (ref "U1") (pin "6") (pinfunction "-_6") (pintype "passive"))
    )
    (net (code "56") (name "Net-(U1A-OUT1)") (class "Default")
      (node (ref "R14") (pin "2") (pinfunction "2_2") (pintype "passive"))
      (node (ref "R3") (pin "1") (pinfunction "1_1") (pintype "passive"))
      (node (ref "R6") (pin "1") (pinfunction "1_1") (pintype "passive"))
      (node (ref "U1") (pin "1") (pinfunction "OUT1_1") (pintype "passive"))
    )
    (net (code "57") (name "Net-(U4A--)") (class "Default")
      (node (ref "R33") (pin "1") (pinfunction "1_1") (pintype "passive"))
      (node (ref "R35") (pin "2") (pinfunction "2_2") (pintype "passive"))
      (node (ref "U4") (pin "2") (pinfunction "-_2") (pintype "passive"))
    )
    (net (code "58") (name "Net-(U4A-OUT1)") (class "Default")
      (node (ref "R29") (pin "1") (pinfunction "1_1") (pintype "passive"))
      (node (ref "R31") (pin "1") (pinfunction "1_1") (pintype "passive"))
      (node (ref "U4") (pin "1") (pinfunction "OUT1_1") (pintype "passive"))
    )
    (net (code "59") (name "Vout") (class "Default")
      (node (ref "D15") (pin "2") (pinfunction "K_2") (pintype "passive"))
      (node (ref "J3") (pin "4") (pinfunction "4_4") (pintype "passive"))
      (node (ref "LED3") (pin "1") (pinfunction "1_1") (pintype "passive"))
      (node (ref "R36") (pin "2") (pinfunction "2_2") (pintype "passive"))
    )
    (net (code "60") (name "unconnected-(J3-Pad3)") (class "Default")
      (node (ref "J3") (pin "3") (pinfunction "3_3") (pintype "passive"))
    )
    (net (code "61") (name "unconnected-(P1-Pad3)") (class "Default")
      (node (ref "P1") (pin "3") (pinfunction "3_3") (pintype "passive"))
    )
    (net (code "62") (name "unconnected-(S1-Pad1)") (class "Default")
      (node (ref "S1") (pin "1") (pinfunction "1_1") (pintype "passive"))
    )
    (net (code "63") (name "unconnected-(S3-Pad1)") (class "Default")
      (node (ref "S3") (pin "1") (pinfunction "1_1") (pintype "passive"))
    )
  )
)
